# CT-ARM.net
KiCad netlist of a schematic drawn in EAGLE
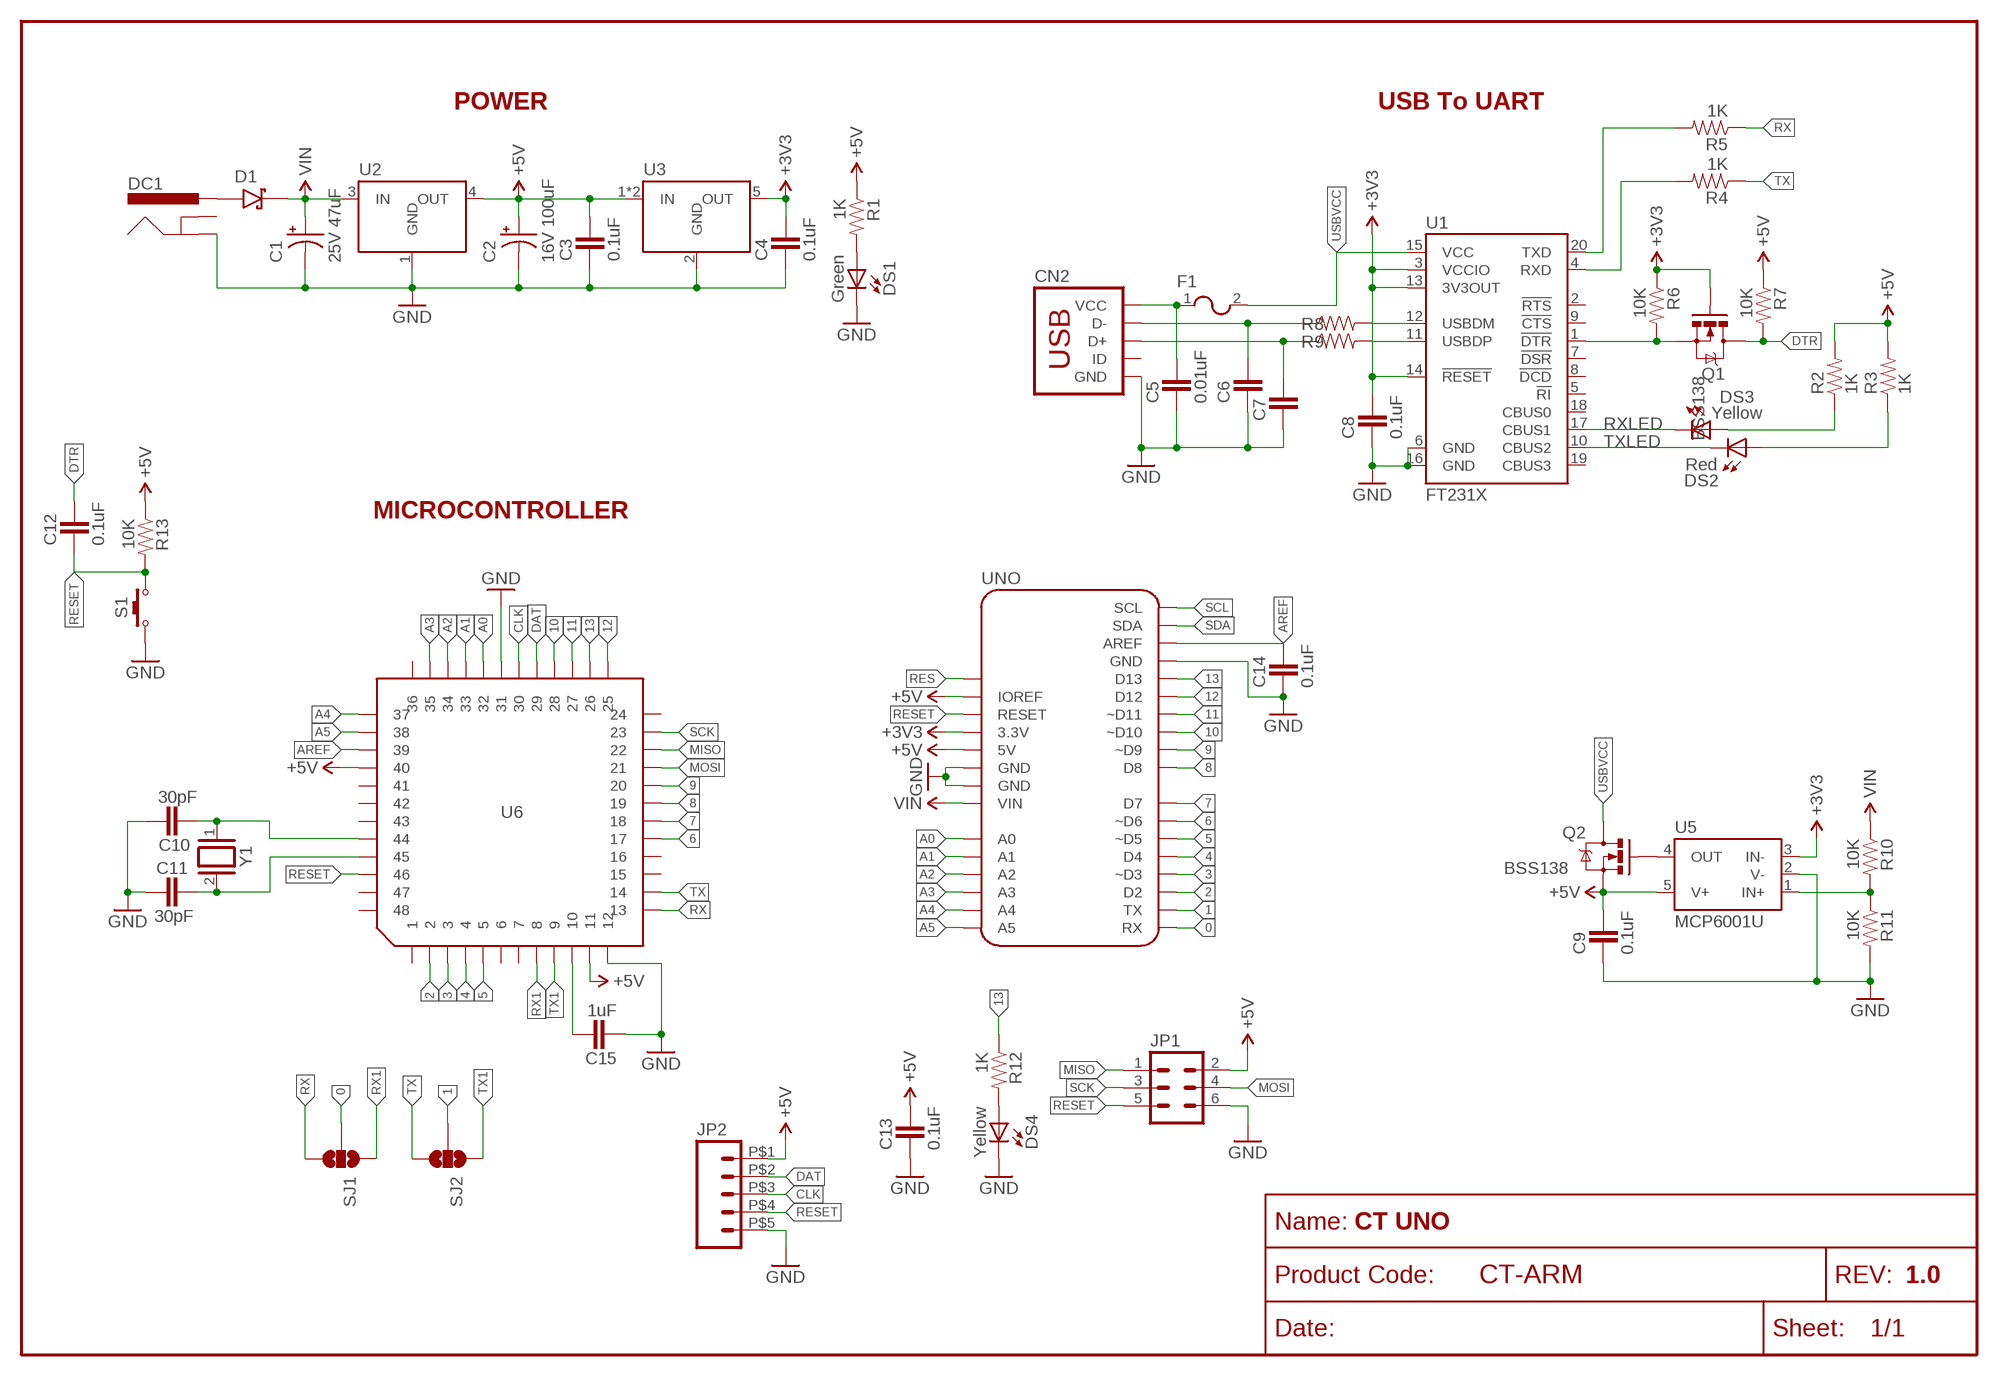
[diagram p0: schematic, sheet 1]

(export (version "E")
  (design (tool "Eeschema 10.0.6"))
  (components
    (comp (ref "C1")
      (value "25V 47uF")
      (footprint "eagle-import:ECAP-CHEMICON-F")
      (libsource (lib "eagle-import") (part "CAP-E-ALUMINIUM_(CHEMICON-F55)_25V47UF"))
    )
    (comp (ref "C2")
      (value "16V 100uF")
      (footprint "eagle-import:ECAP-CHEMICON-F")
      (libsource (lib "eagle-import") (part "CAP-E-ALUMINIUM_(CHEMICON-F55)_16V100UF"))
    )
    (comp (ref "C3")
      (value "0.1uF")
      (footprint "eagle-import:2012")
      (libsource (lib "eagle-import") (part "CAP-C_(2012)_0.1UF"))
    )
    (comp (ref "C4")
      (value "0.1uF")
      (footprint "eagle-import:2012")
      (libsource (lib "eagle-import") (part "CAP-C_(2012)_0.1UF"))
    )
    (comp (ref "C5")
      (value "0.01uF")
      (footprint "eagle-import:2012")
      (libsource (lib "eagle-import") (part "CAP-C_(2012)_0.01UF"))
    )
    (comp (ref "C6")
      (value "CAP-C_(2012)")
      (footprint "eagle-import:2012")
      (libsource (lib "eagle-import") (part "CAP-C_(2012)"))
    )
    (comp (ref "C7")
      (value "CAP-C_(2012)")
      (footprint "eagle-import:2012")
      (libsource (lib "eagle-import") (part "CAP-C_(2012)"))
    )
    (comp (ref "C8")
      (value "0.1uF")
      (footprint "eagle-import:2012")
      (libsource (lib "eagle-import") (part "CAP-C_(2012)_0.1UF"))
    )
    (comp (ref "C9")
      (value "0.1uF")
      (footprint "eagle-import:2012")
      (libsource (lib "eagle-import") (part "CAP-C_(2012)_0.1UF"))
    )
    (comp (ref "C10")
      (value "30pF")
      (footprint "eagle-import:2012")
      (libsource (lib "eagle-import") (part "CAP-C_(2012)_30PF"))
    )
    (comp (ref "C11")
      (value "30pF")
      (footprint "eagle-import:2012")
      (libsource (lib "eagle-import") (part "CAP-C_(2012)_30PF"))
    )
    (comp (ref "C12")
      (value "0.1uF")
      (footprint "eagle-import:2012")
      (libsource (lib "eagle-import") (part "CAP-C_(2012)_0.1UF"))
    )
    (comp (ref "C13")
      (value "0.1uF")
      (footprint "eagle-import:2012")
      (libsource (lib "eagle-import") (part "CAP-C_(2012)_0.1UF"))
    )
    (comp (ref "C14")
      (value "0.1uF")
      (footprint "eagle-import:2012")
      (libsource (lib "eagle-import") (part "CAP-C_(2012)_0.1UF"))
    )
    (comp (ref "C15")
      (value "1uF")
      (footprint "eagle-import:2012")
      (libsource (lib "eagle-import") (part "CAP-C_(2012)_1UF"))
    )
    (comp (ref "CN2")
      (value "USB-5PIN_(MICRO-B-REC)")
      (footprint "eagle-import:USB-MICRO-B-REC")
      (libsource (lib "eagle-import") (part "USB-5PIN_(MICRO-B-REC)"))
    )
    (comp (ref "D1")
      (value "40V 1A")
      (footprint "eagle-import:D-SMA")
      (fields (field (name "MPN") "MBRA140T"))
      (libsource (lib "eagle-import") (part "DIODE-SCHOTTKY_(SMA)_MBRA140T"))
    )
    (comp (ref "DC1")
      (value "DC_POWER_JACK_(PTH)")
      (footprint "eagle-import:DC_PLUG_PTH")
      (libsource (lib "eagle-import") (part "DC_POWER_JACK_(PTH)"))
    )
    (comp (ref "DS1")
      (value "Green")
      (footprint "eagle-import:LED-3216")
      (libsource (lib "eagle-import") (part "LED_(3216)_GREEN"))
    )
    (comp (ref "DS2")
      (value "Red")
      (footprint "eagle-import:LED-3216")
      (libsource (lib "eagle-import") (part "LED_(3216)_RED"))
    )
    (comp (ref "DS3")
      (value "Yellow")
      (footprint "eagle-import:LED-3216")
      (libsource (lib "eagle-import") (part "LED_(3216)_YELLOW"))
    )
    (comp (ref "DS4")
      (value "Yellow")
      (footprint "eagle-import:LED-3216")
      (libsource (lib "eagle-import") (part "LED_(3216)_YELLOW"))
    )
    (comp (ref "F1")
      (value "500mA")
      (footprint "eagle-import:4532")
      (fields (field (name "MF") "Bourns") (field (name "MPN") "MSMF050"))
      (libsource (lib "eagle-import") (part "FUSE_(4532)"))
    )
    (comp (ref "JP1")
      (value "3/40 Ways")
      (footprint "eagle-import:HDR-M2X03")
      (libsource (lib "eagle-import") (part "HEADER-2X03_(MALE)"))
    )
    (comp (ref "JP2")
      (value "HEADER-1X05_(NOSILK)")
      (footprint "eagle-import:HDR-M1X05-NOSILK")
      (libsource (lib "eagle-import") (part "HEADER-1X05_(NOSILK)"))
    )
    (comp (ref "Q1")
      (value "50V 220mA")
      (footprint "eagle-import:SOT-23")
      (fields (field (name "MPN") "BSS138"))
      (libsource (lib "eagle-import") (part "MOSFET-N_(SOT-23)_BSS138"))
    )
    (comp (ref "Q2")
      (value "50V 220mA")
      (footprint "eagle-import:SOT-23")
      (fields (field (name "MPN") "BSS138"))
      (libsource (lib "eagle-import") (part "MOSFET-N_(SOT-23)_BSS138"))
    )
    (comp (ref "R1")
      (value "1K")
      (footprint "eagle-import:2012")
      (libsource (lib "eagle-import") (part "RESISTOR_(2012)_1K"))
    )
    (comp (ref "R2")
      (value "1K")
      (footprint "eagle-import:2012")
      (libsource (lib "eagle-import") (part "RESISTOR_(2012)_1K"))
    )
    (comp (ref "R3")
      (value "1K")
      (footprint "eagle-import:2012")
      (libsource (lib "eagle-import") (part "RESISTOR_(2012)_1K"))
    )
    (comp (ref "R4")
      (value "1K")
      (footprint "eagle-import:2012")
      (libsource (lib "eagle-import") (part "RESISTOR_(2012)_1K"))
    )
    (comp (ref "R5")
      (value "1K")
      (footprint "eagle-import:2012")
      (libsource (lib "eagle-import") (part "RESISTOR_(2012)_1K"))
    )
    (comp (ref "R6")
      (value "10K")
      (footprint "eagle-import:2012")
      (libsource (lib "eagle-import") (part "RESISTOR_(2012)_10K"))
    )
    (comp (ref "R7")
      (value "10K")
      (footprint "eagle-import:2012")
      (libsource (lib "eagle-import") (part "RESISTOR_(2012)_10K"))
    )
    (comp (ref "R8")
      (value "RESISTOR_(2012)")
      (footprint "eagle-import:2012")
      (libsource (lib "eagle-import") (part "RESISTOR_(2012)"))
    )
    (comp (ref "R9")
      (value "RESISTOR_(2012)")
      (footprint "eagle-import:2012")
      (libsource (lib "eagle-import") (part "RESISTOR_(2012)"))
    )
    (comp (ref "R10")
      (value "10K")
      (footprint "eagle-import:2012")
      (libsource (lib "eagle-import") (part "RESISTOR_(2012)_10K"))
    )
    (comp (ref "R11")
      (value "10K")
      (footprint "eagle-import:2012")
      (libsource (lib "eagle-import") (part "RESISTOR_(2012)_10K"))
    )
    (comp (ref "R12")
      (value "1K")
      (footprint "eagle-import:2012")
      (libsource (lib "eagle-import") (part "RESISTOR_(2012)_1K"))
    )
    (comp (ref "R13")
      (value "10K")
      (footprint "eagle-import:2012")
      (libsource (lib "eagle-import") (part "RESISTOR_(2012)_10K"))
    )
    (comp (ref "S1")
      (value "SW-PB_(KAN0444)")
      (footprint "eagle-import:S-SW-PBM-KAN0444")
      (libsource (lib "eagle-import") (part "SW-PB_(KAN0444)"))
    )
    (comp (ref "SJ1")
      (value "SOLDERJUMPER_2WAYS")
      (footprint "eagle-import:SJ_3")
      (libsource (lib "eagle-import") (part "SOLDERJUMPER_2WAYS"))
    )
    (comp (ref "SJ2")
      (value "SOLDERJUMPER_2WAYS")
      (footprint "eagle-import:SJ_3")
      (libsource (lib "eagle-import") (part "SOLDERJUMPER_2WAYS"))
    )
    (comp (ref "U1")
      (value "FT231XS")
      (footprint "eagle-import:SSOP20_L")
      (fields (field (name "MPN") "FT231X"))
      (libsource (lib "eagle-import") (part "FT231XS"))
    )
    (comp (ref "U2")
      (value "5V")
      (footprint "eagle-import:DPAK")
      (libsource (lib "eagle-import") (part "VREG_(DPAK-GOI)_1117-5.0"))
    )
    (comp (ref "U3")
      (value "3.3V 500mA")
      (footprint "eagle-import:SOT-23-5")
      (libsource (lib "eagle-import") (part "VREG_(SOT-23-5)"))
    )
    (comp (ref "U5")
      (value "5 Pins")
      (footprint "eagle-import:SOT-23-5")
      (fields (field (name "MPN") "MCP6001U"))
      (libsource (lib "eagle-import") (part "MCP6001U_(SOT)"))
    )
    (comp (ref "U6")
      (value "NUC-48PIN_(48PIN)")
      (footprint "eagle-import:LQFP48")
      (libsource (lib "eagle-import") (part "NUC-48PIN_(48PIN)"))
    )
    (comp (ref "UNO")
      (value "ARDUINO-UNO-SHEILD_(UNO)")
      (footprint "eagle-import:ARDUINO-UNO-SHIELD")
      (libsource (lib "eagle-import") (part "ARDUINO-UNO-SHEILD_(UNO)"))
    )
    (comp (ref "Y1")
      (value "XTAL_(SMD-HC49UP)")
      (footprint "eagle-import:XTAL-HC49UP")
      (libsource (lib "eagle-import") (part "XTAL_(SMD-HC49UP)"))
    )
  )
  (nets
    (net (code "1") (name "+3V3") (class "Default")
      (node (ref "C4") (pin "1") (pinfunction "1_1") (pintype "passive"))
      (node (ref "C8") (pin "1") (pinfunction "1_1") (pintype "passive"))
      (node (ref "Q1") (pin "1") (pinfunction "G_1") (pintype "input"))
      (node (ref "R6") (pin "1") (pinfunction "1_1") (pintype "passive"))
      (node (ref "U1") (pin "13") (pinfunction "3V3OUT_13") (pintype "bidirectional"))
      (node (ref "U1") (pin "14") (pinfunction "~{RESET}_14") (pintype "bidirectional"))
      (node (ref "U1") (pin "3") (pinfunction "VCCIO_3") (pintype "bidirectional"))
      (node (ref "U3") (pin "5") (pinfunction "OUT_5") (pintype "bidirectional"))
      (node (ref "U5") (pin "3") (pinfunction "IN-_3") (pintype "bidirectional"))
      (node (ref "UNO") (pin "4") (pinfunction "3.3V_4") (pintype "bidirectional"))
    )
    (net (code "2") (name "+5V") (class "Default")
      (node (ref "C13") (pin "1") (pinfunction "1_1") (pintype "passive"))
      (node (ref "C2") (pin "+") (pinfunction "+_+") (pintype "passive"))
      (node (ref "C3") (pin "1") (pinfunction "1_1") (pintype "passive"))
      (node (ref "C9") (pin "1") (pinfunction "1_1") (pintype "passive"))
      (node (ref "JP1") (pin "2") (pinfunction "2_2") (pintype "passive"))
      (node (ref "JP2") (pin "P$1") (pinfunction "1_P$1") (pintype "passive"))
      (node (ref "Q2") (pin "2") (pinfunction "S_2") (pintype "bidirectional"))
      (node (ref "R1") (pin "1") (pinfunction "1_1") (pintype "passive"))
      (node (ref "R13") (pin "1") (pinfunction "1_1") (pintype "passive"))
      (node (ref "R2") (pin "2") (pinfunction "2_2") (pintype "passive"))
      (node (ref "R3") (pin "2") (pinfunction "2_2") (pintype "passive"))
      (node (ref "R7") (pin "1") (pinfunction "1_1") (pintype "passive"))
      (node (ref "U2") (pin "4") (pinfunction "OUT_4") (pintype "bidirectional"))
      (node (ref "U3") (pin "1") (pinfunction "IN_1") (pintype "input"))
      (node (ref "U3") (pin "3") (pinfunction "IN_3") (pintype "input"))
      (node (ref "U5") (pin "5") (pinfunction "V+_5") (pintype "bidirectional"))
      (node (ref "U6") (pin "11") (pinfunction "11_11") (pintype "bidirectional"))
      (node (ref "U6") (pin "40") (pinfunction "40_40") (pintype "bidirectional"))
      (node (ref "UNO") (pin "2") (pinfunction "IOREF_2") (pintype "bidirectional"))
      (node (ref "UNO") (pin "5") (pinfunction "5V_5") (pintype "bidirectional"))
    )
    (net (code "3") (name "0") (class "Default")
      (node (ref "SJ1") (pin "2") (pinfunction "2_2") (pintype "passive"))
      (node (ref "UNO") (pin "15") (pinfunction "RX_15") (pintype "bidirectional"))
    )
    (net (code "4") (name "1") (class "Default")
      (node (ref "SJ2") (pin "2") (pinfunction "2_2") (pintype "passive"))
      (node (ref "UNO") (pin "16") (pinfunction "TX_16") (pintype "bidirectional"))
    )
    (net (code "5") (name "2") (class "Default")
      (node (ref "U6") (pin "2") (pinfunction "2_2") (pintype "bidirectional"))
      (node (ref "UNO") (pin "17") (pinfunction "D2_17") (pintype "bidirectional"))
    )
    (net (code "6") (name "3") (class "Default")
      (node (ref "U6") (pin "3") (pinfunction "3_3") (pintype "bidirectional"))
      (node (ref "UNO") (pin "18") (pinfunction "~{D3}_18") (pintype "bidirectional"))
    )
    (net (code "7") (name "4") (class "Default")
      (node (ref "U6") (pin "4") (pinfunction "4_4") (pintype "bidirectional"))
      (node (ref "UNO") (pin "19") (pinfunction "D4_19") (pintype "bidirectional"))
    )
    (net (code "8") (name "5") (class "Default")
      (node (ref "U6") (pin "5") (pinfunction "5_5") (pintype "bidirectional"))
      (node (ref "UNO") (pin "20") (pinfunction "~{D5}_20") (pintype "bidirectional"))
    )
    (net (code "9") (name "6") (class "Default")
      (node (ref "U6") (pin "17") (pinfunction "17_17") (pintype "bidirectional"))
      (node (ref "UNO") (pin "21") (pinfunction "~{D6}_21") (pintype "bidirectional"))
    )
    (net (code "10") (name "7") (class "Default")
      (node (ref "U6") (pin "18") (pinfunction "18_18") (pintype "bidirectional"))
      (node (ref "UNO") (pin "22") (pinfunction "D7_22") (pintype "bidirectional"))
    )
    (net (code "11") (name "8") (class "Default")
      (node (ref "U6") (pin "19") (pinfunction "19_19") (pintype "bidirectional"))
      (node (ref "UNO") (pin "23") (pinfunction "D8_23") (pintype "bidirectional"))
    )
    (net (code "12") (name "9") (class "Default")
      (node (ref "U6") (pin "20") (pinfunction "20_20") (pintype "bidirectional"))
      (node (ref "UNO") (pin "24") (pinfunction "~{D9}_24") (pintype "bidirectional"))
    )
    (net (code "13") (name "10") (class "Default")
      (node (ref "U6") (pin "28") (pinfunction "28_28") (pintype "bidirectional"))
      (node (ref "UNO") (pin "25") (pinfunction "~{D10}_25") (pintype "bidirectional"))
    )
    (net (code "14") (name "11") (class "Default")
      (node (ref "U6") (pin "27") (pinfunction "27_27") (pintype "bidirectional"))
      (node (ref "UNO") (pin "26") (pinfunction "~{D11}_26") (pintype "bidirectional"))
    )
    (net (code "15") (name "12") (class "Default")
      (node (ref "U6") (pin "25") (pinfunction "25_25") (pintype "bidirectional"))
      (node (ref "UNO") (pin "27") (pinfunction "D12_27") (pintype "bidirectional"))
    )
    (net (code "16") (name "13") (class "Default")
      (node (ref "R12") (pin "1") (pinfunction "1_1") (pintype "passive"))
      (node (ref "U6") (pin "26") (pinfunction "26_26") (pintype "bidirectional"))
      (node (ref "UNO") (pin "28") (pinfunction "D13_28") (pintype "bidirectional"))
    )
    (net (code "17") (name "A0") (class "Default")
      (node (ref "U6") (pin "32") (pinfunction "32_32") (pintype "bidirectional"))
      (node (ref "UNO") (pin "9") (pinfunction "A0_9") (pintype "bidirectional"))
    )
    (net (code "18") (name "A1") (class "Default")
      (node (ref "U6") (pin "33") (pinfunction "33_33") (pintype "bidirectional"))
      (node (ref "UNO") (pin "10") (pinfunction "A1_10") (pintype "bidirectional"))
    )
    (net (code "19") (name "A2") (class "Default")
      (node (ref "U6") (pin "34") (pinfunction "34_34") (pintype "bidirectional"))
      (node (ref "UNO") (pin "11") (pinfunction "A2_11") (pintype "bidirectional"))
    )
    (net (code "20") (name "A3") (class "Default")
      (node (ref "U6") (pin "35") (pinfunction "35_35") (pintype "bidirectional"))
      (node (ref "UNO") (pin "12") (pinfunction "A3_12") (pintype "bidirectional"))
    )
    (net (code "21") (name "A4") (class "Default")
      (node (ref "U6") (pin "37") (pinfunction "37_37") (pintype "bidirectional"))
      (node (ref "UNO") (pin "13") (pinfunction "A4_13") (pintype "bidirectional"))
    )
    (net (code "22") (name "A5") (class "Default")
      (node (ref "U6") (pin "38") (pinfunction "38_38") (pintype "bidirectional"))
      (node (ref "UNO") (pin "14") (pinfunction "A5_14") (pintype "bidirectional"))
    )
    (net (code "23") (name "AREF") (class "Default")
      (node (ref "C14") (pin "1") (pinfunction "1_1") (pintype "passive"))
      (node (ref "U6") (pin "39") (pinfunction "39_39") (pintype "bidirectional"))
      (node (ref "UNO") (pin "30") (pinfunction "AREF_30") (pintype "bidirectional"))
    )
    (net (code "24") (name "CLK") (class "Default")
      (node (ref "JP2") (pin "P$3") (pinfunction "3_P$3") (pintype "passive"))
      (node (ref "U6") (pin "30") (pinfunction "30_30") (pintype "bidirectional"))
    )
    (net (code "25") (name "DAT") (class "Default")
      (node (ref "JP2") (pin "P$2") (pinfunction "2_P$2") (pintype "passive"))
      (node (ref "U6") (pin "29") (pinfunction "29_29") (pintype "bidirectional"))
    )
    (net (code "26") (name "DTR") (class "Default")
      (node (ref "C12") (pin "1") (pinfunction "1_1") (pintype "passive"))
      (node (ref "Q1") (pin "3") (pinfunction "D_3") (pintype "bidirectional"))
      (node (ref "R7") (pin "2") (pinfunction "2_2") (pintype "passive"))
    )
    (net (code "27") (name "GND") (class "Default")
      (node (ref "C1") (pin "-") (pinfunction "-_-") (pintype "passive"))
      (node (ref "C10") (pin "1") (pinfunction "1_1") (pintype "passive"))
      (node (ref "C11") (pin "2") (pinfunction "2_2") (pintype "passive"))
      (node (ref "C13") (pin "2") (pinfunction "2_2") (pintype "passive"))
      (node (ref "C14") (pin "2") (pinfunction "2_2") (pintype "passive"))
      (node (ref "C15") (pin "2") (pinfunction "2_2") (pintype "passive"))
      (node (ref "C2") (pin "-") (pinfunction "-_-") (pintype "passive"))
      (node (ref "C3") (pin "2") (pinfunction "2_2") (pintype "passive"))
      (node (ref "C4") (pin "2") (pinfunction "2_2") (pintype "passive"))
      (node (ref "C5") (pin "2") (pinfunction "2_2") (pintype "passive"))
      (node (ref "C6") (pin "2") (pinfunction "2_2") (pintype "passive"))
      (node (ref "C7") (pin "2") (pinfunction "2_2") (pintype "passive"))
      (node (ref "C8") (pin "2") (pinfunction "2_2") (pintype "passive"))
      (node (ref "C9") (pin "2") (pinfunction "2_2") (pintype "passive"))
      (node (ref "CN2") (pin "GND1") (pinfunction "GND_GND1") (pintype "passive"))
      (node (ref "DC1") (pin "1") (pinfunction "GND_1") (pintype "bidirectional"))
      (node (ref "DS1") (pin "C") (pinfunction "C_C") (pintype "bidirectional"))
      (node (ref "DS4") (pin "C") (pinfunction "C_C") (pintype "bidirectional"))
      (node (ref "JP1") (pin "6") (pinfunction "6_6") (pintype "passive"))
      (node (ref "JP2") (pin "P$5") (pinfunction "5_P$5") (pintype "passive"))
      (node (ref "R11") (pin "2") (pinfunction "2_2") (pintype "passive"))
      (node (ref "S1") (pin "P$1") (pinfunction "1_P$1") (pintype "passive"))
      (node (ref "U1") (pin "16") (pinfunction "GND_16") (pintype "bidirectional"))
      (node (ref "U1") (pin "6") (pinfunction "GND_6") (pintype "bidirectional"))
      (node (ref "U2") (pin "1") (pinfunction "GND_1") (pintype "bidirectional"))
      (node (ref "U3") (pin "2") (pinfunction "GND_2") (pintype "bidirectional"))
      (node (ref "U5") (pin "2") (pinfunction "V-_2") (pintype "bidirectional"))
      (node (ref "U6") (pin "12") (pinfunction "12_12") (pintype "bidirectional"))
      (node (ref "U6") (pin "31") (pinfunction "31_31") (pintype "bidirectional"))
      (node (ref "UNO") (pin "29") (pinfunction "GND_29") (pintype "bidirectional"))
      (node (ref "UNO") (pin "6") (pinfunction "GND_6") (pintype "bidirectional"))
      (node (ref "UNO") (pin "7") (pinfunction "GND_7") (pintype "bidirectional"))
    )
    (net (code "28") (name "MISO") (class "Default")
      (node (ref "JP1") (pin "1") (pinfunction "1_1") (pintype "passive"))
      (node (ref "U6") (pin "22") (pinfunction "22_22") (pintype "bidirectional"))
    )
    (net (code "29") (name "MOSI") (class "Default")
      (node (ref "JP1") (pin "4") (pinfunction "4_4") (pintype "passive"))
      (node (ref "U6") (pin "21") (pinfunction "21_21") (pintype "bidirectional"))
    )
    (net (code "30") (name "Net-(C10-Pad2)") (class "Default")
      (node (ref "C10") (pin "2") (pinfunction "2_2") (pintype "passive"))
      (node (ref "U6") (pin "44") (pinfunction "44_44") (pintype "bidirectional"))
      (node (ref "Y1") (pin "1") (pinfunction "1_1") (pintype "bidirectional"))
    )
    (net (code "31") (name "Net-(C11-Pad1)") (class "Default")
      (node (ref "C11") (pin "1") (pinfunction "1_1") (pintype "passive"))
      (node (ref "U6") (pin "45") (pinfunction "45_45") (pintype "bidirectional"))
      (node (ref "Y1") (pin "2") (pinfunction "2_2") (pintype "bidirectional"))
    )
    (net (code "32") (name "Net-(C15-Pad1)") (class "Default")
      (node (ref "C15") (pin "1") (pinfunction "1_1") (pintype "passive"))
      (node (ref "U6") (pin "10") (pinfunction "10_10") (pintype "bidirectional"))
    )
    (net (code "33") (name "Net-(CN2-D+)") (class "Default")
      (node (ref "C7") (pin "1") (pinfunction "1_1") (pintype "passive"))
      (node (ref "CN2") (pin "D+1") (pinfunction "D+_D+1") (pintype "passive"))
      (node (ref "R9") (pin "1") (pinfunction "1_1") (pintype "passive"))
    )
    (net (code "34") (name "Net-(CN2-D-)") (class "Default")
      (node (ref "C6") (pin "1") (pinfunction "1_1") (pintype "passive"))
      (node (ref "CN2") (pin "D-1") (pinfunction "D-_D-1") (pintype "passive"))
      (node (ref "R8") (pin "1") (pinfunction "1_1") (pintype "passive"))
    )
    (net (code "35") (name "Net-(CN2-VCC)") (class "Default")
      (node (ref "C5") (pin "1") (pinfunction "1_1") (pintype "passive"))
      (node (ref "CN2") (pin "VBUS1") (pinfunction "VCC_VBUS1") (pintype "passive"))
      (node (ref "F1") (pin "1") (pinfunction "1_1") (pintype "bidirectional"))
    )
    (net (code "36") (name "Net-(DC1-PWR)") (class "Default")
      (node (ref "D1") (pin "A") (pinfunction "A_A") (pintype "bidirectional"))
      (node (ref "DC1") (pin "2") (pinfunction "PWR_2") (pintype "bidirectional"))
    )
    (net (code "37") (name "Net-(DS1-PadA)") (class "Default")
      (node (ref "DS1") (pin "A") (pinfunction "A_A") (pintype "bidirectional"))
      (node (ref "R1") (pin "2") (pinfunction "2_2") (pintype "passive"))
    )
    (net (code "38") (name "Net-(DS2-PadA)") (class "Default")
      (node (ref "DS2") (pin "A") (pinfunction "A_A") (pintype "bidirectional"))
      (node (ref "R3") (pin "1") (pinfunction "1_1") (pintype "passive"))
    )
    (net (code "39") (name "Net-(DS3-PadA)") (class "Default")
      (node (ref "DS3") (pin "A") (pinfunction "A_A") (pintype "bidirectional"))
      (node (ref "R2") (pin "1") (pinfunction "1_1") (pintype "passive"))
    )
    (net (code "40") (name "Net-(DS4-PadA)") (class "Default")
      (node (ref "DS4") (pin "A") (pinfunction "A_A") (pintype "bidirectional"))
      (node (ref "R12") (pin "2") (pinfunction "2_2") (pintype "passive"))
    )
    (net (code "41") (name "Net-(Q1-S)") (class "Default")
      (node (ref "Q1") (pin "2") (pinfunction "S_2") (pintype "bidirectional"))
      (node (ref "R6") (pin "2") (pinfunction "2_2") (pintype "passive"))
      (node (ref "U1") (pin "1") (pinfunction "~{DTR}_1") (pintype "bidirectional"))
    )
    (net (code "42") (name "Net-(Q2-G)") (class "Default")
      (node (ref "Q2") (pin "1") (pinfunction "G_1") (pintype "input"))
      (node (ref "U5") (pin "4") (pinfunction "OUT_4") (pintype "bidirectional"))
    )
    (net (code "43") (name "Net-(U1-CBUS1)") (class "Default")
      (node (ref "DS3") (pin "C") (pinfunction "C_C") (pintype "bidirectional"))
      (node (ref "U1") (pin "17") (pinfunction "CBUS1_17") (pintype "bidirectional"))
    )
    (net (code "44") (name "Net-(U1-CBUS2)") (class "Default")
      (node (ref "DS2") (pin "C") (pinfunction "C_C") (pintype "bidirectional"))
      (node (ref "U1") (pin "10") (pinfunction "CBUS2_10") (pintype "bidirectional"))
    )
    (net (code "45") (name "Net-(U1-RXD)") (class "Default")
      (node (ref "R4") (pin "2") (pinfunction "2_2") (pintype "passive"))
      (node (ref "U1") (pin "4") (pinfunction "RXD_4") (pintype "bidirectional"))
    )
    (net (code "46") (name "Net-(U1-TXD)") (class "Default")
      (node (ref "R5") (pin "2") (pinfunction "2_2") (pintype "passive"))
      (node (ref "U1") (pin "20") (pinfunction "TXD_20") (pintype "bidirectional"))
    )
    (net (code "47") (name "Net-(U1-USBDM)") (class "Default")
      (node (ref "R8") (pin "2") (pinfunction "2_2") (pintype "passive"))
      (node (ref "U1") (pin "12") (pinfunction "USBDM_12") (pintype "bidirectional"))
    )
    (net (code "48") (name "Net-(U1-USBDP)") (class "Default")
      (node (ref "R9") (pin "2") (pinfunction "2_2") (pintype "passive"))
      (node (ref "U1") (pin "11") (pinfunction "USBDP_11") (pintype "bidirectional"))
    )
    (net (code "49") (name "Net-(U5-IN+)") (class "Default")
      (node (ref "R10") (pin "2") (pinfunction "2_2") (pintype "passive"))
      (node (ref "R11") (pin "1") (pinfunction "1_1") (pintype "passive"))
      (node (ref "U5") (pin "1") (pinfunction "IN+_1") (pintype "bidirectional"))
    )
    (net (code "50") (name "RES") (class "Default") (node (ref "UNO") (pin "1") (pintype "bidirectional")))
    (net (code "51") (name "RESET") (class "Default")
      (node (ref "C12") (pin "2") (pinfunction "2_2") (pintype "passive"))
      (node (ref "JP1") (pin "5") (pinfunction "5_5") (pintype "passive"))
      (node (ref "JP2") (pin "P$4") (pinfunction "4_P$4") (pintype "passive"))
      (node (ref "R13") (pin "2") (pinfunction "2_2") (pintype "passive"))
      (node (ref "S1") (pin "P$2") (pinfunction "2_P$2") (pintype "passive"))
      (node (ref "U6") (pin "46") (pinfunction "46_46") (pintype "bidirectional"))
      (node (ref "UNO") (pin "3") (pinfunction "RESET_3") (pintype "bidirectional"))
    )
    (net (code "52") (name "RX") (class "Default")
      (node (ref "R5") (pin "1") (pinfunction "1_1") (pintype "passive"))
      (node (ref "SJ1") (pin "3") (pinfunction "3_3") (pintype "passive"))
      (node (ref "U6") (pin "13") (pinfunction "13_13") (pintype "bidirectional"))
    )
    (net (code "53") (name "RX1") (class "Default")
      (node (ref "SJ1") (pin "1") (pinfunction "1_1") (pintype "passive"))
      (node (ref "U6") (pin "8") (pinfunction "8_8") (pintype "bidirectional"))
    )
    (net (code "54") (name "SCK") (class "Default")
      (node (ref "JP1") (pin "3") (pinfunction "3_3") (pintype "passive"))
      (node (ref "U6") (pin "23") (pinfunction "23_23") (pintype "bidirectional"))
    )
    (net (code "55") (name "SCL") (class "Default")
      (node (ref "UNO") (pin "32") (pinfunction "SCL_32") (pintype "bidirectional"))
    )
    (net (code "56") (name "SDA") (class "Default")
      (node (ref "UNO") (pin "31") (pinfunction "SDA_31") (pintype "bidirectional"))
    )
    (net (code "57") (name "TX") (class "Default")
      (node (ref "R4") (pin "1") (pinfunction "1_1") (pintype "passive"))
      (node (ref "SJ2") (pin "3") (pinfunction "3_3") (pintype "passive"))
      (node (ref "U6") (pin "14") (pinfunction "14_14") (pintype "bidirectional"))
    )
    (net (code "58") (name "TX1") (class "Default")
      (node (ref "SJ2") (pin "1") (pinfunction "1_1") (pintype "passive"))
      (node (ref "U6") (pin "9") (pinfunction "9_9") (pintype "bidirectional"))
    )
    (net (code "59") (name "USBVCC") (class "Default")
      (node (ref "F1") (pin "2") (pinfunction "2_2") (pintype "bidirectional"))
      (node (ref "Q2") (pin "3") (pinfunction "D_3") (pintype "bidirectional"))
      (node (ref "U1") (pin "15") (pinfunction "VCC_15") (pintype "bidirectional"))
    )
    (net (code "60") (name "VIN") (class "Default")
      (node (ref "C1") (pin "+") (pinfunction "+_+") (pintype "passive"))
      (node (ref "D1") (pin "C") (pinfunction "C_C") (pintype "bidirectional"))
      (node (ref "R10") (pin "1") (pinfunction "1_1") (pintype "passive"))
      (node (ref "U2") (pin "3") (pinfunction "IN_3") (pintype "input"))
      (node (ref "UNO") (pin "8") (pinfunction "VIN_8") (pintype "bidirectional"))
    )
    (net (code "61") (name "unconnected-(CN2-ID-PadID1)") (class "Default")
      (node (ref "CN2") (pin "ID1") (pinfunction "ID_ID1") (pintype "passive"))
    )
    (net (code "62") (name "unconnected-(DC1-GNDBREAK-Pad3)") (class "Default")
      (node (ref "DC1") (pin "3") (pinfunction "GNDBREAK_3") (pintype "bidirectional"))
    )
    (net (code "63") (name "unconnected-(U1-CBUS0-Pad18)") (class "Default")
      (node (ref "U1") (pin "18") (pinfunction "CBUS0_18") (pintype "bidirectional"))
    )
    (net (code "64") (name "unconnected-(U1-CBUS3-Pad19)") (class "Default")
      (node (ref "U1") (pin "19") (pinfunction "CBUS3_19") (pintype "bidirectional"))
    )
    (net (code "65") (name "unconnected-(U1-~{CTS}-Pad9)") (class "Default")
      (node (ref "U1") (pin "9") (pinfunction "~{CTS}_9") (pintype "bidirectional"))
    )
    (net (code "66") (name "unconnected-(U1-~{DCD}-Pad8)") (class "Default")
      (node (ref "U1") (pin "8") (pinfunction "~{DCD}_8") (pintype "bidirectional"))
    )
    (net (code "67") (name "unconnected-(U1-~{DSR}-Pad7)") (class "Default")
      (node (ref "U1") (pin "7") (pinfunction "~{DSR}_7") (pintype "bidirectional"))
    )
    (net (code "68") (name "unconnected-(U1-~{RI}-Pad5)") (class "Default")
      (node (ref "U1") (pin "5") (pinfunction "~{RI}_5") (pintype "bidirectional"))
    )
    (net (code "69") (name "unconnected-(U1-~{RTS}-Pad2)") (class "Default")
      (node (ref "U1") (pin "2") (pinfunction "~{RTS}_2") (pintype "bidirectional"))
    )
    (net (code "70") (name "unconnected-(U6-Pad1)") (class "Default")
      (node (ref "U6") (pin "1") (pinfunction "1_1") (pintype "bidirectional"))
    )
    (net (code "71") (name "unconnected-(U6-Pad6)") (class "Default")
      (node (ref "U6") (pin "6") (pinfunction "6_6") (pintype "bidirectional"))
    )
    (net (code "72") (name "unconnected-(U6-Pad7)") (class "Default")
      (node (ref "U6") (pin "7") (pinfunction "7_7") (pintype "bidirectional"))
    )
    (net (code "73") (name "unconnected-(U6-Pad15)") (class "Default")
      (node (ref "U6") (pin "15") (pinfunction "15_15") (pintype "bidirectional"))
    )
    (net (code "74") (name "unconnected-(U6-Pad16)") (class "Default")
      (node (ref "U6") (pin "16") (pinfunction "16_16") (pintype "bidirectional"))
    )
    (net (code "75") (name "unconnected-(U6-Pad24)") (class "Default")
      (node (ref "U6") (pin "24") (pinfunction "24_24") (pintype "bidirectional"))
    )
    (net (code "76") (name "unconnected-(U6-Pad36)") (class "Default")
      (node (ref "U6") (pin "36") (pinfunction "36_36") (pintype "bidirectional"))
    )
    (net (code "77") (name "unconnected-(U6-Pad41)") (class "Default")
      (node (ref "U6") (pin "41") (pinfunction "41_41") (pintype "bidirectional"))
    )
    (net (code "78") (name "unconnected-(U6-Pad42)") (class "Default")
      (node (ref "U6") (pin "42") (pinfunction "42_42") (pintype "bidirectional"))
    )
    (net (code "79") (name "unconnected-(U6-Pad43)") (class "Default")
      (node (ref "U6") (pin "43") (pinfunction "43_43") (pintype "bidirectional"))
    )
    (net (code "80") (name "unconnected-(U6-Pad47)") (class "Default")
      (node (ref "U6") (pin "47") (pinfunction "47_47") (pintype "bidirectional"))
    )
    (net (code "81") (name "unconnected-(U6-Pad48)") (class "Default")
      (node (ref "U6") (pin "48") (pinfunction "48_48") (pintype "bidirectional"))
    )
  )
)
